# Power.net
KiCad netlist of a schematic drawn in Altium Designer
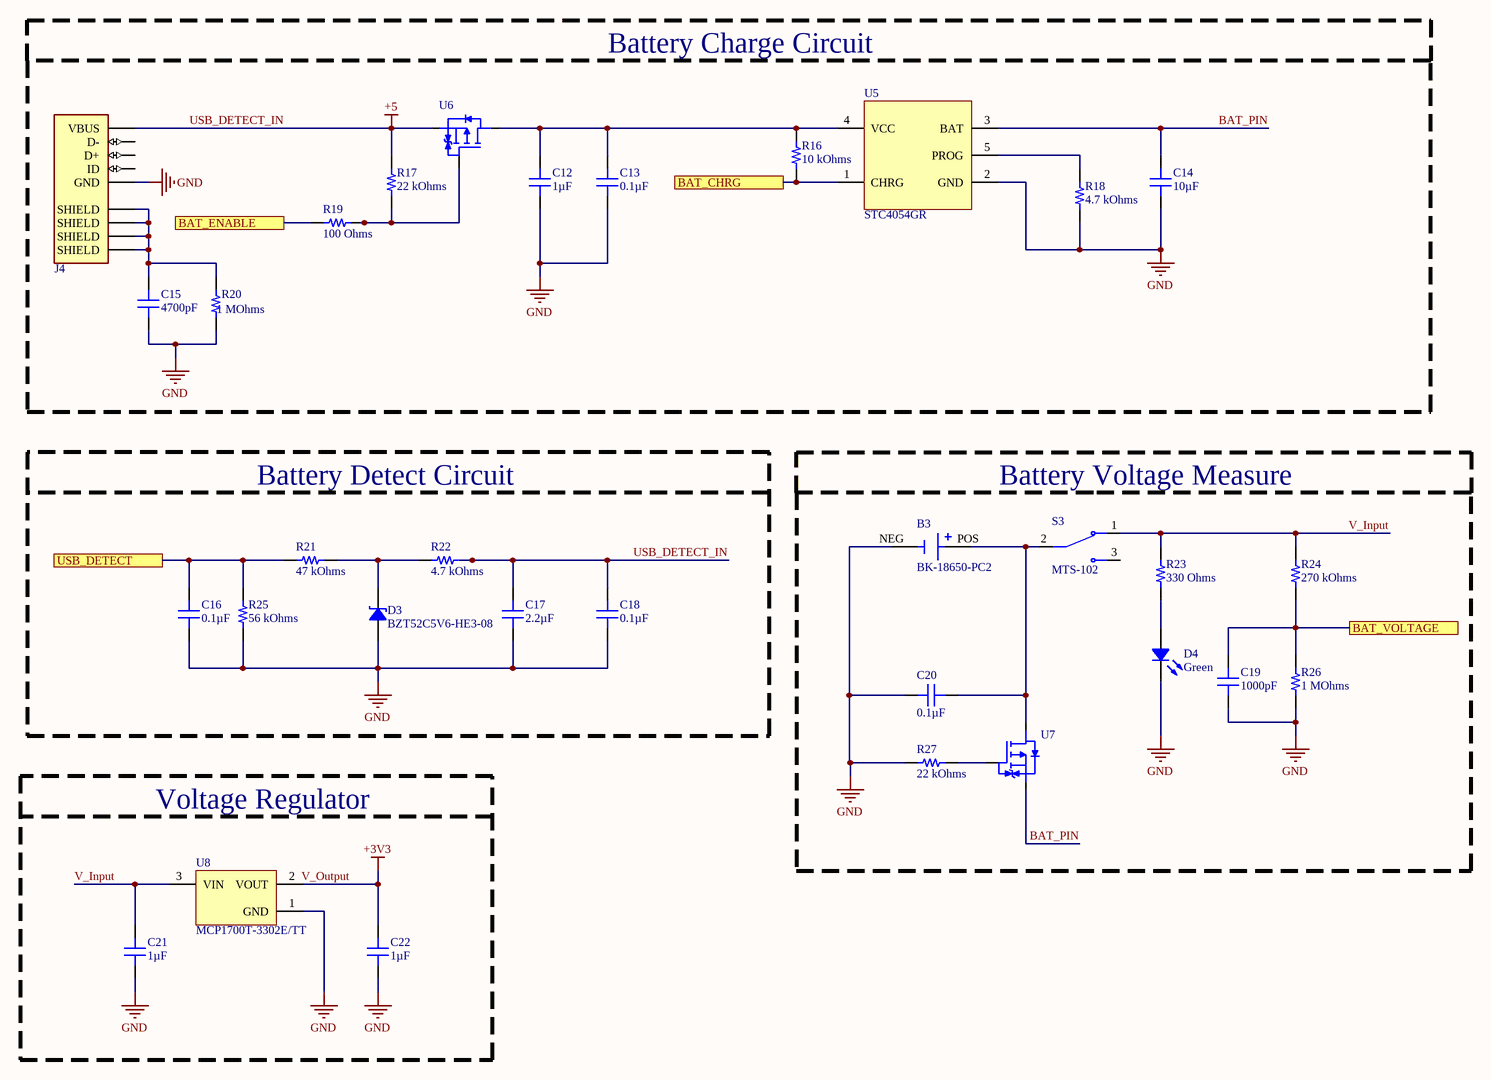
[diagram p0: Power.SchDoc]

(export (version "E")
  (design (tool "Eeschema 10.0.6"))
  (components
    (comp (ref "B3")
      (value "BK-18650-PC2")
      (footprint "BK-16850-PC2")
      (description "Battery Holder 18650 Pc Pin")
      (fields (field (name "MANUFACTURER") "Memory Protection Devices"))
      (libsource (lib "MyLibrary_Integrated") (part "BK-18650-PC2"))
    )
    (comp (ref "C12")
      (value "1µF")
      (footprint "CAP 0603_1608")
      (description "CAP CER 0603 1UF 16V X7R 10%")
      (fields (field (name "PART NUMBER") "C0603C105K4RACAUTO") (field (name "MANUFACTURER") "KEMET"))
      (libsource (lib "Celestial Altium Library - altium_library") (part "Capacitor"))
    )
    (comp (ref "C13")
      (value "0.1µF")
      (footprint "CAP 0603_1608")
      (description "CAP CER 0.10UF 16V X7R 0603")
      (fields (field (name "PART NUMBER") "0603Y0160104KXT") (field (name "MANUFACTURER") "Knowles Syfer"))
      (libsource (lib "Celestial Altium Library - altium_library") (part "Capacitor"))
    )
    (comp (ref "C14")
      (value "10µF")
      (footprint "CAP 0603_1608")
      (description "CAP CER 10UF 6.3V X5R 0603")
      (fields
        (field (name "PART NUMBER") "GRM188R60J106ME47D")
        (field (name "MANUFACTURER") "Murata Electronics")
      )
      (libsource (lib "Celestial Altium Library - altium_library") (part "Capacitor"))
    )
    (comp (ref "C15")
      (value "4700pF")
      (footprint "CAP 0603_1608")
      (description "CAP CER 0603 4.7NF 16V X7R 10%")
      (fields (field (name "PART NUMBER") "C0603C472K4RECAUTO") (field (name "MANUFACTURER") "KEMET"))
      (libsource (lib "Celestial Altium Library - altium_library") (part "Capacitor"))
    )
    (comp (ref "C16")
      (value "0.1µF")
      (footprint "CAP 0603_1608")
      (description "CAP CER 0.10UF 16V X7R 0603")
      (fields (field (name "PART NUMBER") "0603Y0160104KXT") (field (name "MANUFACTURER") "Knowles Syfer"))
      (libsource (lib "Celestial Altium Library - altium_library") (part "Capacitor"))
    )
    (comp (ref "C17")
      (value "2.2µF")
      (footprint "CAP 0603_1608")
      (description "CAP CER 2.2UF 16V Y5V 0603")
      (fields (field (name "PART NUMBER") "CC0603ZRY5V7BB225") (field (name "MANUFACTURER") "Yageo"))
      (libsource (lib "Celestial Altium Library - altium_library") (part "Capacitor"))
    )
    (comp (ref "C18")
      (value "0.1µF")
      (footprint "CAP 0603_1608")
      (description "CAP CER 0.10UF 16V X7R 0603")
      (fields (field (name "PART NUMBER") "0603Y0160104KXT") (field (name "MANUFACTURER") "Knowles Syfer"))
      (libsource (lib "Celestial Altium Library - altium_library") (part "Capacitor"))
    )
    (comp (ref "C19")
      (value "1000pF")
      (footprint "CAP 0603_1608")
      (description "CAP CER 0603 1NF 16V X7R 10%")
      (fields (field (name "PART NUMBER") "C0603C102K4RECAUTO") (field (name "MANUFACTURER") "KEMET"))
      (libsource (lib "Celestial Altium Library - altium_library") (part "Capacitor"))
    )
    (comp (ref "C20")
      (value "0.1µF")
      (footprint "CAP 0603_1608")
      (description "CAP CER 0.10UF 16V X7R 0603")
      (fields (field (name "PART NUMBER") "0603Y0160104KXT") (field (name "MANUFACTURER") "Knowles Syfer"))
      (libsource (lib "Celestial Altium Library - altium_library") (part "Capacitor"))
    )
    (comp (ref "C21")
      (value "1µF")
      (footprint "CAP 0603_1608")
      (description "CAP CER 0603 1UF 16V X7R 10%")
      (fields (field (name "PART NUMBER") "C0603C105K4RACAUTO") (field (name "MANUFACTURER") "KEMET"))
      (libsource (lib "Celestial Altium Library - altium_library") (part "Capacitor"))
    )
    (comp (ref "C22")
      (value "1µF")
      (footprint "CAP 0603_1608")
      (description "CAP CER 0603 1UF 16V X7R 10%")
      (fields (field (name "PART NUMBER") "C0603C105K4RACAUTO") (field (name "MANUFACTURER") "KEMET"))
      (libsource (lib "Celestial Altium Library - altium_library") (part "Capacitor"))
    )
    (comp (ref "D3")
      (value "BZT52C5V6-HE3-08")
      (footprint "SOD-123")
      (description "DIODE ZENER 5.6V 410MW SOD123")
      (fields
        (field (name "MANUFACTURER") "Vishay Semiconductor Diodes Division")
        (field (name "TOLERANCE") "±5%")
      )
      (libsource (lib "Celestial Altium Library - altium_library") (part "Diode Zener"))
    )
    (comp (ref "D4")
      (value "Green")
      (footprint "LED 1206_3216 YELLOW")
      (description "LED YELLOW 1206 SMD")
      (fields (field (name "PART NUMBER") "5990240007F") (field (name "MANUFACTURER") "Dialight"))
      (libsource (lib "Celestial Altium Library - altium_library") (part "LED"))
    )
    (comp (ref "J4")
      (value "USB2066-05-RBHM-15-STB-00-00-A")
      (footprint "USB Mini-B")
      (description "Conn Mini USB Type B RCP 5 POS 0.8mm Solder RA SMD 5 Terminal 1 Port T/R")
      (fields (field (name "MANUFACTURER") "GCT (GLOBAL CONNECTOR TECHNOLOGY)"))
      (libsource (lib "MyLibrary_Integrated") (part "USB2066-05-RBHM-15-STB-00-00-A"))
    )
    (comp (ref "R16")
      (value "10 kOhms")
      (footprint "RES 0603_1608")
      (description "RES SMD 10K OHM 0.1% 1/16W 0603")
      (fields
        (field (name "PART NUMBER") "CPF0603B10KE")
        (field (name "MANUFACTURER") "TE Connectivity Passive Product")
      )
      (libsource (lib "Celestial Altium Library - altium_library") (part "Resistor"))
    )
    (comp (ref "R17")
      (value "22 kOhms")
      (footprint "RES 0603_1608")
      (description "RES SMD 22K OHM 5% 1/10W 0603")
      (fields (field (name "PART NUMBER") "AC0603JR-0722KL") (field (name "MANUFACTURER") "Yageo"))
      (libsource (lib "Celestial Altium Library - altium_library") (part "Resistor"))
    )
    (comp (ref "R18")
      (value "4.7 kOhms")
      (footprint "RES 0603_1608")
      (description "RES SMD 4.7K OHM 0.1% 1/10W 0603")
      (fields
        (field (name "PART NUMBER") "ERA-3AEB472V")
        (field (name "MANUFACTURER") "Panasonic Electronic Components")
      )
      (libsource (lib "Celestial Altium Library - altium_library") (part "Resistor"))
    )
    (comp (ref "R19")
      (value "100 Ohms")
      (footprint "RES 0603_1608")
      (description "RES 100 OHM 0.1% 1/16W 0603")
      (fields
        (field (name "PART NUMBER") "RNCS0603BKE100R")
        (field (name "MANUFACTURER") "Stackpole Electronics Inc")
      )
      (libsource (lib "Celestial Altium Library - altium_library") (part "Resistor"))
    )
    (comp (ref "R20")
      (value "1 MOhms")
      (footprint "RES 0603_1608")
      (description "RES 1M OHM 1% 1/10W 0603")
      (fields
        (field (name "PART NUMBER") "RMCF0603FT1M00")
        (field (name "MANUFACTURER") "Stackpole Electronics Inc")
      )
      (libsource (lib "Celestial Altium Library - altium_library") (part "Resistor"))
    )
    (comp (ref "R21")
      (value "47 kOhms")
      (footprint "RES 0603_1608")
      (description "RES SMD 47K OHM 5% 1/4W 0603")
      (fields (field (name "PART NUMBER") "RCS060347K0JNEA") (field (name "MANUFACTURER") "Vishay Dale"))
      (libsource (lib "Celestial Altium Library - altium_library") (part "Resistor"))
    )
    (comp (ref "R22")
      (value "4.7 kOhms")
      (footprint "RES 0603_1608")
      (description "RES SMD 4.7K OHM 0.1% 1/10W 0603")
      (fields
        (field (name "PART NUMBER") "ERA-3AEB472V")
        (field (name "MANUFACTURER") "Panasonic Electronic Components")
      )
      (libsource (lib "Celestial Altium Library - altium_library") (part "Resistor"))
    )
    (comp (ref "R23")
      (value "330 Ohms")
      (footprint "RES 0603_1608")
      (description "RES SMD 330 OHM 1% 1/10W 0603")
      (fields (field (name "PART NUMBER") "AC0603FR-07330RL") (field (name "MANUFACTURER") "Yageo"))
      (libsource (lib "Celestial Altium Library - altium_library") (part "Resistor"))
    )
    (comp (ref "R24")
      (value "270 kOhms")
      (footprint "RES 0603_1608")
      (description "CRGP 0603 270K 1%")
      (fields
        (field (name "PART NUMBER") "CRGP0603F270K")
        (field (name "MANUFACTURER") "TE Connectivity Passive Product")
      )
      (libsource (lib "Celestial Altium Library - altium_library") (part "Resistor"))
    )
    (comp (ref "R25")
      (value "56 kOhms")
      (footprint "RES 0603_1608")
      (description "RES SMD 56K OHM 1% 1/10W 0603")
      (fields (field (name "PART NUMBER") "AC0603FR-0756KL") (field (name "MANUFACTURER") "Yageo"))
      (libsource (lib "Celestial Altium Library - altium_library") (part "Resistor"))
    )
    (comp (ref "R26")
      (value "1 MOhms")
      (footprint "RES 0603_1608")
      (description "RES 1M OHM 1% 1/10W 0603")
      (fields
        (field (name "PART NUMBER") "RMCF0603FT1M00")
        (field (name "MANUFACTURER") "Stackpole Electronics Inc")
      )
      (libsource (lib "Celestial Altium Library - altium_library") (part "Resistor"))
    )
    (comp (ref "R27")
      (value "22 kOhms")
      (footprint "RES 0603_1608")
      (description "RES SMD 22K OHM 5% 1/10W 0603")
      (fields (field (name "PART NUMBER") "AC0603JR-0722KL") (field (name "MANUFACTURER") "Yageo"))
      (libsource (lib "Celestial Altium Library - altium_library") (part "Resistor"))
    )
    (comp (ref "S3")
      (value "MTS-102")
      (footprint "MTS-102 (Toggle)")
      (libsource (lib "MyLibrary_Integrated") (part "MTS-102"))
    )
    (comp (ref "U5")
      (value "STC4054GR")
      (footprint "TSOT-23")
      (description "STC4054 Series 6.5 V 800 mA Standalone Linear Li-Ion Battery Charger - TSOT-23-5")
      (fields (field (name "MANUFACTURER") "STMicroelectronics"))
      (libsource (lib "MyLibrary_Integrated") (part "STC4054GR"))
    )
    (comp (ref "U6")
      (value "SSM3J338R,LF")
      (footprint "SOT-23-3")
      (description "Small-Signal Mosfet Pch Sot23F, Vdss=-12V, Id=-6A, Rdson: 20Ohm Rohs Compliant: Yes")
      (fields (field (name "MANUFACTURER") "Toshiba"))
      (libsource (lib "MyLibrary_Integrated") (part "SSM3J338R,LF"))
    )
    (comp (ref "U7")
      (value "SSM3J338R,LF")
      (footprint "SOT-23-3")
      (description "Small-Signal Mosfet Pch Sot23F, Vdss=-12V, Id=-6A, Rdson: 20Ohm Rohs Compliant: Yes")
      (fields (field (name "MANUFACTURER") "Toshiba"))
      (libsource (lib "MyLibrary_Integrated") (part "SSM3J338R,LF"))
    )
    (comp (ref "U8")
      (value "MCP1700T-3302E/TT")
      (footprint "SOT-23-3")
      (description "Pwr Sply Func, Voltage Regulator, LDO, SOT-23, PD 369.6mW, VO 3.3V, Regline +/-0.75%/V")
      (fields (field (name "MANUFACTURER") "Microchip"))
      (libsource (lib "MyLibrary_Integrated") (part "MCP1700T-3302E/TT"))
    )
  )
  (nets
    (net (code "1") (name "+3V3") (class "Default")
      (node (ref "C22") (pin "2") (pinfunction "2_2") (pintype "passive"))
      (node (ref "U8") (pin "2") (pinfunction "VOUT_2") (pintype "power_in"))
    )
    (net (code "2") (name "+5") (class "Default")
      (node (ref "C17") (pin "2") (pinfunction "2_2") (pintype "passive"))
      (node (ref "C18") (pin "2") (pinfunction "2_2") (pintype "passive"))
      (node (ref "J4") (pin "1") (pinfunction "VBUS_1") (pintype "power_in"))
      (node (ref "R17") (pin "2") (pinfunction "2_2") (pintype "passive"))
      (node (ref "R22") (pin "1") (pinfunction "1_1") (pintype "passive"))
      (node (ref "U6") (pin "2") (pinfunction "S_2") (pintype "passive"))
    )
    (net (code "3") (name "/BAT_CHRG") (class "Default")
      (node (ref "R16") (pin "1") (pinfunction "1_1") (pintype "passive"))
      (node (ref "U5") (pin "1") (pinfunction "CHRG_1") (pintype "passive"))
    )
    (net (code "4") (name "/BAT_ENABLE") (class "Default")
      (node (ref "R19") (pin "1") (pinfunction "1_1") (pintype "passive"))
    )
    (net (code "5") (name "/BAT_PIN") (class "Default")
      (node (ref "C14") (pin "2") (pinfunction "2_2") (pintype "passive"))
      (node (ref "U5") (pin "3") (pinfunction "BAT_3") (pintype "passive"))
      (node (ref "U7") (pin "2") (pinfunction "S_2") (pintype "passive"))
    )
    (net (code "6") (name "/BAT_VOLTAGE") (class "Default")
      (node (ref "C19") (pin "2") (pinfunction "2_2") (pintype "passive"))
      (node (ref "R24") (pin "1") (pinfunction "1_1") (pintype "passive"))
      (node (ref "R26") (pin "2") (pinfunction "2_2") (pintype "passive"))
    )
    (net (code "7") (name "/USB_DETECT") (class "Default")
      (node (ref "C16") (pin "2") (pinfunction "2_2") (pintype "passive"))
      (node (ref "R21") (pin "1") (pinfunction "1_1") (pintype "passive"))
      (node (ref "R25") (pin "2") (pinfunction "2_2") (pintype "passive"))
    )
    (net (code "8") (name "/V_Input") (class "Default")
      (node (ref "C21") (pin "2") (pinfunction "2_2") (pintype "passive"))
      (node (ref "R23") (pin "2") (pinfunction "2_2") (pintype "passive"))
      (node (ref "R24") (pin "2") (pinfunction "2_2") (pintype "passive"))
      (node (ref "S3") (pin "1") (pinfunction "1_1") (pintype "passive"))
      (node (ref "U8") (pin "3") (pinfunction "VIN_3") (pintype "power_in"))
    )
    (net (code "9") (name "GND") (class "Default")
      (node (ref "B3") (pin "NEG") (pinfunction "NEG_NEG") (pintype "passive"))
      (node (ref "C12") (pin "1") (pinfunction "1_1") (pintype "passive"))
      (node (ref "C13") (pin "1") (pinfunction "1_1") (pintype "passive"))
      (node (ref "C14") (pin "1") (pinfunction "1_1") (pintype "passive"))
      (node (ref "C15") (pin "1") (pinfunction "1_1") (pintype "passive"))
      (node (ref "C16") (pin "1") (pinfunction "1_1") (pintype "passive"))
      (node (ref "C17") (pin "1") (pinfunction "1_1") (pintype "passive"))
      (node (ref "C18") (pin "1") (pinfunction "1_1") (pintype "passive"))
      (node (ref "C19") (pin "1") (pinfunction "1_1") (pintype "passive"))
      (node (ref "C20") (pin "1") (pinfunction "1_1") (pintype "passive"))
      (node (ref "C21") (pin "1") (pinfunction "1_1") (pintype "passive"))
      (node (ref "C22") (pin "1") (pinfunction "1_1") (pintype "passive"))
      (node (ref "D3") (pin "1") (pinfunction "1_1") (pintype "passive"))
      (node (ref "D4") (pin "2") (pinfunction "2_2") (pintype "passive"))
      (node (ref "J4") (pin "5") (pinfunction "GND_5") (pintype "power_in"))
      (node (ref "R18") (pin "1") (pinfunction "1_1") (pintype "passive"))
      (node (ref "R20") (pin "1") (pinfunction "1_1") (pintype "passive"))
      (node (ref "R25") (pin "1") (pinfunction "1_1") (pintype "passive"))
      (node (ref "R26") (pin "1") (pinfunction "1_1") (pintype "passive"))
      (node (ref "R27") (pin "1") (pinfunction "1_1") (pintype "passive"))
      (node (ref "U5") (pin "2") (pinfunction "GND_2") (pintype "passive"))
      (node (ref "U8") (pin "1") (pinfunction "GND_1") (pintype "power_in"))
    )
    (net (code "10") (name "Net-(C15-Pad2)") (class "Default")
      (node (ref "C15") (pin "2") (pinfunction "2_2") (pintype "passive"))
      (node (ref "J4") (pin "6") (pinfunction "SHIELD_6") (pintype "power_in"))
      (node (ref "J4") (pin "7") (pinfunction "SHIELD_7") (pintype "power_in"))
      (node (ref "J4") (pin "8") (pinfunction "SHIELD_8") (pintype "power_in"))
      (node (ref "J4") (pin "9") (pinfunction "SHIELD_9") (pintype "power_in"))
      (node (ref "R20") (pin "2") (pinfunction "2_2") (pintype "passive"))
    )
    (net (code "11") (name "Net-(D3-Pad2)") (class "Default")
      (node (ref "D3") (pin "2") (pinfunction "2_2") (pintype "passive"))
      (node (ref "R21") (pin "2") (pinfunction "2_2") (pintype "passive"))
      (node (ref "R22") (pin "2") (pinfunction "2_2") (pintype "passive"))
    )
    (net (code "12") (name "Net-(D4-Pad1)") (class "Default")
      (node (ref "D4") (pin "1") (pinfunction "1_1") (pintype "passive"))
      (node (ref "R23") (pin "1") (pinfunction "1_1") (pintype "passive"))
    )
    (net (code "13") (name "Net-(U5-PROG)") (class "Default")
      (node (ref "R18") (pin "2") (pinfunction "2_2") (pintype "passive"))
      (node (ref "U5") (pin "5") (pinfunction "PROG_5") (pintype "passive"))
    )
    (net (code "14") (name "Net-(U5-VCC)") (class "Default")
      (node (ref "C12") (pin "2") (pinfunction "2_2") (pintype "passive"))
      (node (ref "C13") (pin "2") (pinfunction "2_2") (pintype "passive"))
      (node (ref "R16") (pin "2") (pinfunction "2_2") (pintype "passive"))
      (node (ref "U5") (pin "4") (pinfunction "VCC_4") (pintype "passive"))
      (node (ref "U6") (pin "3") (pinfunction "D_3") (pintype "passive"))
    )
    (net (code "15") (name "Net-(U6-G)") (class "Default")
      (node (ref "R17") (pin "1") (pinfunction "1_1") (pintype "passive"))
      (node (ref "R19") (pin "2") (pinfunction "2_2") (pintype "passive"))
      (node (ref "U6") (pin "1") (pinfunction "G_1") (pintype "passive"))
    )
    (net (code "16") (name "Net-(U7-D)") (class "Default")
      (node (ref "B3") (pin "POS") (pinfunction "POS_POS") (pintype "passive"))
      (node (ref "C20") (pin "2") (pinfunction "2_2") (pintype "passive"))
      (node (ref "S3") (pin "2") (pinfunction "2_2") (pintype "passive"))
      (node (ref "U7") (pin "3") (pinfunction "D_3") (pintype "passive"))
    )
    (net (code "17") (name "Net-(U7-G)") (class "Default")
      (node (ref "R27") (pin "2") (pinfunction "2_2") (pintype "passive"))
      (node (ref "U7") (pin "1") (pinfunction "G_1") (pintype "passive"))
    )
    (net (code "18") (name "unconnected-(J4-D+-Pad3)") (class "Default")
      (node (ref "J4") (pin "3") (pinfunction "D+_3") (pintype "bidirectional"))
    )
    (net (code "19") (name "unconnected-(J4-D--Pad2)") (class "Default")
      (node (ref "J4") (pin "2") (pinfunction "D-_2") (pintype "bidirectional"))
    )
    (net (code "20") (name "unconnected-(J4-ID-Pad4)") (class "Default")
      (node (ref "J4") (pin "4") (pinfunction "ID_4") (pintype "bidirectional"))
    )
    (net (code "21") (name "unconnected-(S3-Pad3)") (class "Default")
      (node (ref "S3") (pin "3") (pinfunction "3_3") (pintype "passive"))
    )
  )
)
